# ProPrj___2024-09-03.net
KiCad netlist of a schematic drawn in EasyEDA Pro
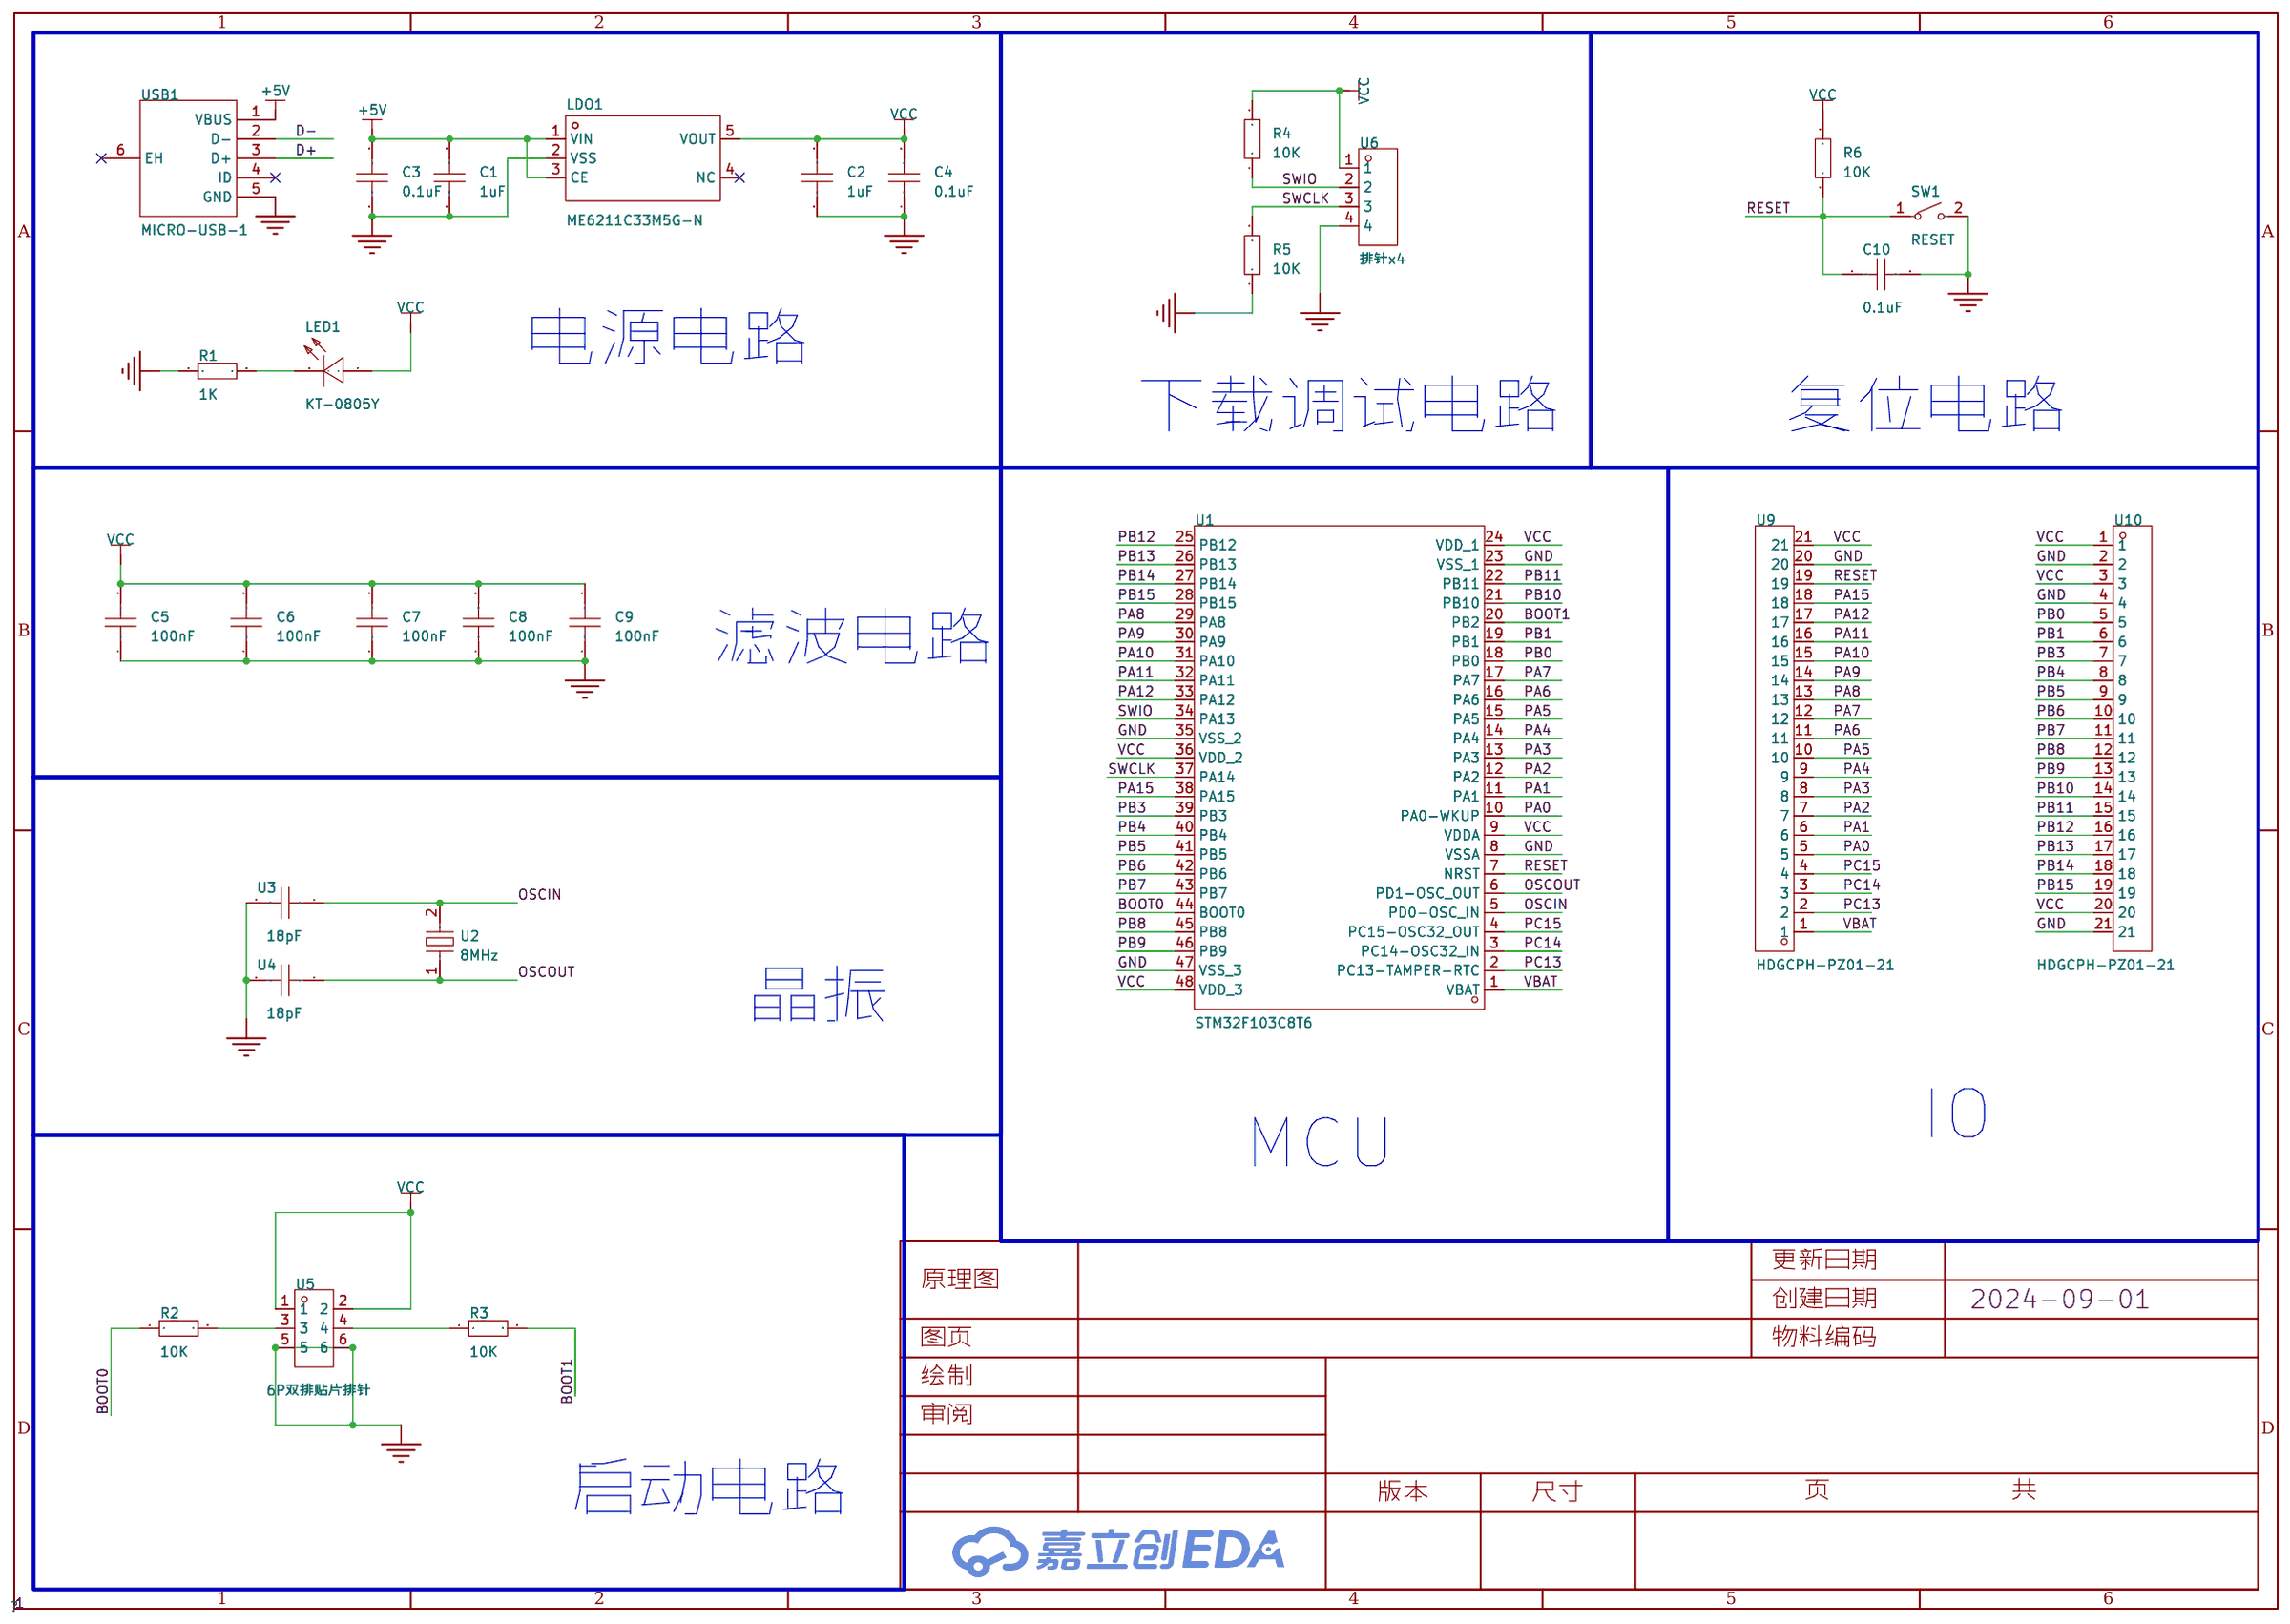
[diagram p0: schematic sheet]

(export (version "E")
  (design (tool "Eeschema 10.0.6"))
  (components
    (comp (ref "C1")
      (value "1uF")
      (footprint "easyedapro:C0603")
      (description "容值:1uF;精度:±10%;额定电压:50V;材质(温度系数):X5R;")
      (fields
        (field (name "Manufacturer Part") "CL10A105KB8NNNC")
        (field (name "Manufacturer") "SAMSUNG(三星)")
      )
      (libsource (lib "easyedapro") (part "CL10A105KB8NNNC"))
    )
    (comp (ref "C2")
      (value "1uF")
      (footprint "easyedapro:C0603")
      (description "容值:1uF;精度:±10%;额定电压:50V;材质(温度系数):X5R;")
      (fields
        (field (name "Manufacturer Part") "CL10A105KB8NNNC")
        (field (name "Manufacturer") "SAMSUNG(三星)")
      )
      (libsource (lib "easyedapro") (part "CL10A105KB8NNNC"))
    )
    (comp (ref "C3")
      (value "0.1uF")
      (footprint "easyedapro:C0603")
      (description "容值:1pF;额定电压:50V;材质(温度系数):C0G;")
      (fields (field (name "Manufacturer Part") "CGJ3E2C0G1H010C080AA") (field (name "Manufacturer") "TDK"))
      (libsource (lib "easyedapro") (part "CGJ3E2C0G1H010C080AA"))
    )
    (comp (ref "C4")
      (value "0.1uF")
      (footprint "easyedapro:C0603")
      (description "容值:1pF;额定电压:50V;材质(温度系数):C0G;")
      (fields (field (name "Manufacturer Part") "CGJ3E2C0G1H010C080AA") (field (name "Manufacturer") "TDK"))
      (libsource (lib "easyedapro") (part "CGJ3E2C0G1H010C080AA"))
    )
    (comp (ref "C5")
      (value "100nF")
      (footprint "easyedapro:C0603")
      (libsource (lib "easyedapro") (part "CapAcitance"))
    )
    (comp (ref "C6")
      (value "100nF")
      (footprint "easyedapro:C0603")
      (libsource (lib "easyedapro") (part "CapAcitance"))
    )
    (comp (ref "C7")
      (value "100nF")
      (footprint "easyedapro:C0603")
      (libsource (lib "easyedapro") (part "CapAcitance"))
    )
    (comp (ref "C8")
      (value "100nF")
      (footprint "easyedapro:C0603")
      (libsource (lib "easyedapro") (part "CapAcitance"))
    )
    (comp (ref "C9")
      (value "100nF")
      (footprint "easyedapro:C0603")
      (libsource (lib "easyedapro") (part "CapAcitance"))
    )
    (comp (ref "C10")
      (value "0.1uF")
      (footprint "easyedapro:C0603")
      (description "容值:1uF;精度:±10%;额定电压:50V;材质(温度系数):X5R;")
      (fields
        (field (name "Manufacturer Part") "CL10A105KB8NNNC")
        (field (name "Manufacturer") "SAMSUNG(三星)")
      )
      (libsource (lib "easyedapro") (part "CL10A105KB8NNNC"))
    )
    (comp (ref "LDO1")
      (value "ME6211C33M5G-N")
      (footprint "easyedapro:SOT-23-5_L3.0-W1.7-P0.95-LS2.8-BL")
      (description "输出类型:固定;最大输入电压:6V;输出电压:3.3V;最大输出电流:500mA;电源纹波抑制比(PSRR):70dB;输出极性:正极;")
      (fields (field (name "Manufacturer") "MICRONE(南京微盟)"))
      (libsource (lib "easyedapro") (part "ME6211C33M5G-N"))
    )
    (comp (ref "LED1")
      (value "KT-0805Y")
      (footprint "easyedapro:LED0805-R-RD")
      (description "发光颜色:黄色;功率:-;正向电流:-;主波长:-;二极管配置:-;透镜颜色:-;色温:-;发光角度:-;载带方式:-;工作温度:-;")
      (fields (field (name "Manufacturer") "KENTO"))
      (libsource (lib "easyedapro") (part "17-21SUYC/TR8"))
    )
    (comp (ref "R1") (value "1K") (footprint "easyedapro:R0603") (libsource (lib "easyedapro") (part "电阻")))
    (comp (ref "R2") (value "10K") (footprint "easyedapro:R0603") (libsource (lib "easyedapro") (part "电阻")))
    (comp (ref "R3") (value "10K") (footprint "easyedapro:R0603") (libsource (lib "easyedapro") (part "电阻")))
    (comp (ref "R4") (value "10K") (footprint "easyedapro:R0603") (libsource (lib "easyedapro") (part "电阻")))
    (comp (ref "R5") (value "10K") (footprint "easyedapro:R0603") (libsource (lib "easyedapro") (part "电阻")))
    (comp (ref "R6") (value "10K") (footprint "easyedapro:R0603") (libsource (lib "easyedapro") (part "电阻")))
    (comp (ref "SW1")
      (value "RESET")
      (footprint "easyedapro:SW-SMD_L6.0-W3.3-LS8.0")
      (libsource (lib "easyedapro") (part "SW_PB2_A1"))
    )
    (comp (ref "U1")
      (value "STM32F103C8T6")
      (footprint "easyedapro:LQFP-48_L7.0-W7.0-P0.50-LS9.0-BL")
      (description "CPU内核:ARM-M3;程序存储容量:64KB;RAM总容量:20KB;GPIO端口数量:37;工作电压范围:2V~3.6V;CPU最大主频:72MHz;程序存储器类型:FLASH;")
      (fields (field (name "Manufacturer") "ST(意法半导体)"))
      (libsource (lib "easyedapro") (part "STM32F103C8T6"))
    )
    (comp (ref "U2")
      (value "8MHz")
      (footprint "easyedapro:HC-49S_L10.6-W4.2-P4.85")
      (description "频率:6.7458MHz;常温频差:±20ppm;外接负载电容:20pF;频率稳定度(全温):±50ppm;")
      (fields
        (field (name "Manufacturer Part") "HY67458M49SOB2T02")
        (field (name "Manufacturer") "Huiyuan crystal(惠源晶工)")
      )
      (libsource (lib "easyedapro") (part "HY67458M49SOB2T02"))
    )
    (comp (ref "U3")
      (value "18pF")
      (footprint "easyedapro:C0603")
      (description "容值:1pF;额定电压:50V;材质(温度系数):C0G;")
      (fields (field (name "Manufacturer Part") "CGJ3E2C0G1H010C080AA") (field (name "Manufacturer") "TDK"))
      (libsource (lib "easyedapro") (part "CGJ3E2C0G1H010C080AA"))
    )
    (comp (ref "U4")
      (value "18pF")
      (footprint "easyedapro:C0603")
      (description "容值:1pF;额定电压:50V;材质(温度系数):C0G;")
      (fields (field (name "Manufacturer Part") "CGJ3E2C0G1H010C080AA") (field (name "Manufacturer") "TDK"))
      (libsource (lib "easyedapro") (part "CGJ3E2C0G1H010C080AA"))
    )
    (comp (ref "U5")
      (value "6P双排贴片排针")
      (footprint "easyedapro:HDR-SMD_6P-P2.54-V-M-R2-C3-LS7.6")
      (libsource (lib "easyedapro") (part "6P双排贴片排针"))
    )
    (comp (ref "U6")
      (value "排针x4")
      (footprint "easyedapro:HDR-TH_4P-P2.54-V-M-1")
      (libsource (lib "easyedapro") (part "排针X4"))
    )
    (comp (ref "U9")
      (value "HDGCPH-PZ01-21")
      (footprint "easyedapro:HDR-TH_21P-P2.54-V-M")
      (fields (field (name "Manufacturer") "HDGC(华德共创)"))
      (libsource (lib "easyedapro") (part "HDGCPH-PZ01- 21"))
    )
    (comp (ref "U10")
      (value "HDGCPH-PZ01-21")
      (footprint "easyedapro:HDR-TH_21P-P2.54-V-M")
      (fields (field (name "Manufacturer") "HDGC(华德共创)"))
      (libsource (lib "easyedapro") (part "HDGCPH-PZ01- 21"))
    )
    (comp (ref "USB1")
      (value "MICRO-USB-1")
      (footprint "easyedapro:MICRO-USB-SMD_C9900008946")
      (libsource (lib "easyedapro") (part "MICRO-USB-1"))
    )
  )
  (nets
    (net (code "1") (name "+5V") (class "Default")
      (node (ref "C1") (pin "2") (pinfunction "2_2") (pintype "unspecified"))
      (node (ref "C3") (pin "2") (pinfunction "2_2") (pintype "unspecified"))
      (node (ref "LDO1") (pin "1") (pinfunction "VIN_1") (pintype "input"))
      (node (ref "LDO1") (pin "3") (pinfunction "CE_3") (pintype "input"))
      (node (ref "USB1") (pin "1") (pinfunction "VBUS_1") (pintype "input"))
    )
    (net (code "2") (name "/BOOT0") (class "Default")
      (node (ref "R2") (pin "1") (pinfunction "1_1") (pintype "input"))
      (node (ref "U1") (pin "44") (pinfunction "BOOT0_44") (pintype "unspecified"))
    )
    (net (code "3") (name "/BOOT1") (class "Default")
      (node (ref "R3") (pin "2") (pinfunction "2_2") (pintype "input"))
      (node (ref "U1") (pin "20") (pinfunction "PB2_20") (pintype "unspecified"))
    )
    (net (code "4") (name "/D+") (class "Default")
      (node (ref "USB1") (pin "3") (pinfunction "D+_3") (pintype "input"))
    )
    (net (code "5") (name "/D-") (class "Default")
      (node (ref "USB1") (pin "2") (pinfunction "D-_2") (pintype "input"))
    )
    (net (code "6") (name "/OSCIN") (class "Default")
      (node (ref "U1") (pin "5") (pinfunction "PD0-OSC_IN_5") (pintype "unspecified"))
      (node (ref "U2") (pin "2") (pinfunction "GND_2") (pintype "input"))
      (node (ref "U3") (pin "1") (pinfunction "1_1") (pintype "unspecified"))
    )
    (net (code "7") (name "/OSCOUT") (class "Default")
      (node (ref "U1") (pin "6") (pinfunction "PD1-OSC_OUT_6") (pintype "unspecified"))
      (node (ref "U2") (pin "1") (pinfunction "1_1") (pintype "input"))
      (node (ref "U4") (pin "1") (pinfunction "1_1") (pintype "unspecified"))
    )
    (net (code "8") (name "/PA0") (class "Default")
      (node (ref "U1") (pin "10") (pinfunction "PA0-WKUP_10") (pintype "unspecified"))
      (node (ref "U9") (pin "5") (pinfunction "5_5") (pintype "unspecified"))
    )
    (net (code "9") (name "/PA1") (class "Default")
      (node (ref "U1") (pin "11") (pinfunction "PA1_11") (pintype "unspecified"))
      (node (ref "U9") (pin "6") (pinfunction "6_6") (pintype "unspecified"))
    )
    (net (code "10") (name "/PA2") (class "Default")
      (node (ref "U1") (pin "12") (pinfunction "PA2_12") (pintype "unspecified"))
      (node (ref "U9") (pin "7") (pinfunction "7_7") (pintype "unspecified"))
    )
    (net (code "11") (name "/PA3") (class "Default")
      (node (ref "U1") (pin "13") (pinfunction "PA3_13") (pintype "unspecified"))
      (node (ref "U9") (pin "8") (pinfunction "8_8") (pintype "unspecified"))
    )
    (net (code "12") (name "/PA4") (class "Default")
      (node (ref "U1") (pin "14") (pinfunction "PA4_14") (pintype "unspecified"))
      (node (ref "U9") (pin "9") (pinfunction "9_9") (pintype "unspecified"))
    )
    (net (code "13") (name "/PA5") (class "Default")
      (node (ref "U1") (pin "15") (pinfunction "PA5_15") (pintype "unspecified"))
      (node (ref "U9") (pin "10") (pinfunction "10_10") (pintype "unspecified"))
    )
    (net (code "14") (name "/PA6") (class "Default")
      (node (ref "U1") (pin "16") (pinfunction "PA6_16") (pintype "unspecified"))
      (node (ref "U9") (pin "11") (pinfunction "11_11") (pintype "unspecified"))
    )
    (net (code "15") (name "/PA7") (class "Default")
      (node (ref "U1") (pin "17") (pinfunction "PA7_17") (pintype "unspecified"))
      (node (ref "U9") (pin "12") (pinfunction "12_12") (pintype "unspecified"))
    )
    (net (code "16") (name "/PA8") (class "Default")
      (node (ref "U1") (pin "29") (pinfunction "PA8_29") (pintype "unspecified"))
      (node (ref "U9") (pin "13") (pinfunction "13_13") (pintype "unspecified"))
    )
    (net (code "17") (name "/PA9") (class "Default")
      (node (ref "U1") (pin "30") (pinfunction "PA9_30") (pintype "unspecified"))
      (node (ref "U9") (pin "14") (pinfunction "14_14") (pintype "unspecified"))
    )
    (net (code "18") (name "/PA10") (class "Default")
      (node (ref "U1") (pin "31") (pinfunction "PA10_31") (pintype "unspecified"))
      (node (ref "U9") (pin "15") (pinfunction "15_15") (pintype "unspecified"))
    )
    (net (code "19") (name "/PA11") (class "Default")
      (node (ref "U1") (pin "32") (pinfunction "PA11_32") (pintype "unspecified"))
      (node (ref "U9") (pin "16") (pinfunction "16_16") (pintype "unspecified"))
    )
    (net (code "20") (name "/PA12") (class "Default")
      (node (ref "U1") (pin "33") (pinfunction "PA12_33") (pintype "unspecified"))
      (node (ref "U9") (pin "17") (pinfunction "17_17") (pintype "unspecified"))
    )
    (net (code "21") (name "/PA15") (class "Default")
      (node (ref "U1") (pin "38") (pinfunction "PA15_38") (pintype "unspecified"))
      (node (ref "U9") (pin "18") (pinfunction "18_18") (pintype "unspecified"))
    )
    (net (code "22") (name "/PB0") (class "Default")
      (node (ref "U1") (pin "18") (pinfunction "PB0_18") (pintype "unspecified"))
      (node (ref "U10") (pin "5") (pinfunction "5_5") (pintype "unspecified"))
    )
    (net (code "23") (name "/PB1") (class "Default")
      (node (ref "U1") (pin "19") (pinfunction "PB1_19") (pintype "unspecified"))
      (node (ref "U10") (pin "6") (pinfunction "6_6") (pintype "unspecified"))
    )
    (net (code "24") (name "/PB3") (class "Default")
      (node (ref "U1") (pin "39") (pinfunction "PB3_39") (pintype "unspecified"))
      (node (ref "U10") (pin "7") (pinfunction "7_7") (pintype "unspecified"))
    )
    (net (code "25") (name "/PB4") (class "Default")
      (node (ref "U1") (pin "40") (pinfunction "PB4_40") (pintype "unspecified"))
      (node (ref "U10") (pin "8") (pinfunction "8_8") (pintype "unspecified"))
    )
    (net (code "26") (name "/PB5") (class "Default")
      (node (ref "U1") (pin "41") (pinfunction "PB5_41") (pintype "unspecified"))
      (node (ref "U10") (pin "9") (pinfunction "9_9") (pintype "unspecified"))
    )
    (net (code "27") (name "/PB6") (class "Default")
      (node (ref "U1") (pin "42") (pinfunction "PB6_42") (pintype "unspecified"))
      (node (ref "U10") (pin "10") (pinfunction "10_10") (pintype "unspecified"))
    )
    (net (code "28") (name "/PB7") (class "Default")
      (node (ref "U1") (pin "43") (pinfunction "PB7_43") (pintype "unspecified"))
      (node (ref "U10") (pin "11") (pinfunction "11_11") (pintype "unspecified"))
    )
    (net (code "29") (name "/PB8") (class "Default")
      (node (ref "U1") (pin "45") (pinfunction "PB8_45") (pintype "unspecified"))
      (node (ref "U10") (pin "12") (pinfunction "12_12") (pintype "unspecified"))
    )
    (net (code "30") (name "/PB9") (class "Default")
      (node (ref "U1") (pin "46") (pinfunction "PB9_46") (pintype "unspecified"))
      (node (ref "U10") (pin "13") (pinfunction "13_13") (pintype "unspecified"))
    )
    (net (code "31") (name "/PB10") (class "Default")
      (node (ref "U1") (pin "21") (pinfunction "PB10_21") (pintype "unspecified"))
      (node (ref "U10") (pin "14") (pinfunction "14_14") (pintype "unspecified"))
    )
    (net (code "32") (name "/PB11") (class "Default")
      (node (ref "U1") (pin "22") (pinfunction "PB11_22") (pintype "unspecified"))
      (node (ref "U10") (pin "15") (pinfunction "15_15") (pintype "unspecified"))
    )
    (net (code "33") (name "/PB12") (class "Default")
      (node (ref "U1") (pin "25") (pinfunction "PB12_25") (pintype "unspecified"))
      (node (ref "U10") (pin "16") (pinfunction "16_16") (pintype "unspecified"))
    )
    (net (code "34") (name "/PB13") (class "Default")
      (node (ref "U1") (pin "26") (pinfunction "PB13_26") (pintype "unspecified"))
      (node (ref "U10") (pin "17") (pinfunction "17_17") (pintype "unspecified"))
    )
    (net (code "35") (name "/PB14") (class "Default")
      (node (ref "U1") (pin "27") (pinfunction "PB14_27") (pintype "unspecified"))
      (node (ref "U10") (pin "18") (pinfunction "18_18") (pintype "unspecified"))
    )
    (net (code "36") (name "/PB15") (class "Default")
      (node (ref "U1") (pin "28") (pinfunction "PB15_28") (pintype "unspecified"))
      (node (ref "U10") (pin "19") (pinfunction "19_19") (pintype "unspecified"))
    )
    (net (code "37") (name "/PC13") (class "Default")
      (node (ref "U1") (pin "2") (pinfunction "PC13-TAMPER-RTC_2") (pintype "unspecified"))
      (node (ref "U9") (pin "2") (pinfunction "2_2") (pintype "unspecified"))
    )
    (net (code "38") (name "/PC14") (class "Default")
      (node (ref "U1") (pin "3") (pinfunction "PC14-OSC32_IN_3") (pintype "unspecified"))
      (node (ref "U9") (pin "3") (pinfunction "3_3") (pintype "unspecified"))
    )
    (net (code "39") (name "/PC15") (class "Default")
      (node (ref "U1") (pin "4") (pinfunction "PC15-OSC32_OUT_4") (pintype "unspecified"))
      (node (ref "U9") (pin "4") (pinfunction "4_4") (pintype "unspecified"))
    )
    (net (code "40") (name "/RESET") (class "Default")
      (node (ref "C10") (pin "1") (pinfunction "1_1") (pintype "unspecified"))
      (node (ref "R6") (pin "1") (pinfunction "1_1") (pintype "input"))
      (node (ref "SW1") (pin "1") (pinfunction "1_1") (pintype "unspecified"))
      (node (ref "U1") (pin "7") (pinfunction "NRST_7") (pintype "unspecified"))
      (node (ref "U9") (pin "19") (pinfunction "19_19") (pintype "unspecified"))
    )
    (net (code "41") (name "/SWCLK") (class "Default")
      (node (ref "R5") (pin "2") (pinfunction "2_2") (pintype "input"))
      (node (ref "U1") (pin "37") (pinfunction "PA14_37") (pintype "unspecified"))
      (node (ref "U6") (pin "3") (pinfunction "3_3") (pintype "unspecified"))
    )
    (net (code "42") (name "/SWIO") (class "Default")
      (node (ref "R4") (pin "1") (pinfunction "1_1") (pintype "input"))
      (node (ref "U1") (pin "34") (pinfunction "PA13_34") (pintype "unspecified"))
      (node (ref "U6") (pin "2") (pinfunction "2_2") (pintype "unspecified"))
    )
    (net (code "43") (name "/VBAT") (class "Default")
      (node (ref "U1") (pin "1") (pinfunction "VBAT_1") (pintype "unspecified"))
      (node (ref "U9") (pin "1") (pinfunction "1_1") (pintype "unspecified"))
    )
    (net (code "44") (name "GND") (class "Default")
      (node (ref "C1") (pin "1") (pinfunction "1_1") (pintype "unspecified"))
      (node (ref "C10") (pin "2") (pinfunction "2_2") (pintype "unspecified"))
      (node (ref "C2") (pin "1") (pinfunction "1_1") (pintype "unspecified"))
      (node (ref "C3") (pin "1") (pinfunction "1_1") (pintype "unspecified"))
      (node (ref "C4") (pin "1") (pinfunction "1_1") (pintype "unspecified"))
      (node (ref "C5") (pin "1") (pinfunction "1_1") (pintype "input"))
      (node (ref "C6") (pin "1") (pinfunction "1_1") (pintype "input"))
      (node (ref "C7") (pin "1") (pinfunction "1_1") (pintype "input"))
      (node (ref "C8") (pin "1") (pinfunction "1_1") (pintype "input"))
      (node (ref "C9") (pin "1") (pinfunction "1_1") (pintype "input"))
      (node (ref "LDO1") (pin "2") (pinfunction "VSS_2") (pintype "input"))
      (node (ref "R1") (pin "1") (pinfunction "1_1") (pintype "input"))
      (node (ref "R5") (pin "1") (pinfunction "1_1") (pintype "input"))
      (node (ref "SW1") (pin "2") (pinfunction "2_2") (pintype "unspecified"))
      (node (ref "U1") (pin "23") (pinfunction "VSS_1_23") (pintype "unspecified"))
      (node (ref "U1") (pin "35") (pinfunction "VSS_2_35") (pintype "unspecified"))
      (node (ref "U1") (pin "47") (pinfunction "VSS_3_47") (pintype "unspecified"))
      (node (ref "U1") (pin "8") (pinfunction "VSSA_8") (pintype "unspecified"))
      (node (ref "U10") (pin "2") (pinfunction "2_2") (pintype "unspecified"))
      (node (ref "U10") (pin "21") (pinfunction "21_21") (pintype "unspecified"))
      (node (ref "U10") (pin "4") (pinfunction "4_4") (pintype "unspecified"))
      (node (ref "U3") (pin "2") (pinfunction "2_2") (pintype "unspecified"))
      (node (ref "U4") (pin "2") (pinfunction "2_2") (pintype "unspecified"))
      (node (ref "U5") (pin "5") (pinfunction "5_5") (pintype "input"))
      (node (ref "U5") (pin "6") (pinfunction "6_6") (pintype "input"))
      (node (ref "U6") (pin "4") (pinfunction "4_4") (pintype "unspecified"))
      (node (ref "U9") (pin "20") (pinfunction "20_20") (pintype "unspecified"))
      (node (ref "USB1") (pin "5") (pinfunction "GND_5") (pintype "input"))
    )
    (net (code "45") (name "Net-(LED1--)") (class "Default")
      (node (ref "LED1") (pin "2") (pinfunction "-_2") (pintype "unspecified"))
      (node (ref "R1") (pin "2") (pinfunction "2_2") (pintype "input"))
    )
    (net (code "46") (name "Net-(R2-Pad2)") (class "Default")
      (node (ref "R2") (pin "2") (pinfunction "2_2") (pintype "input"))
      (node (ref "U5") (pin "3") (pinfunction "3_3") (pintype "input"))
    )
    (net (code "47") (name "Net-(R3-Pad1)") (class "Default")
      (node (ref "R3") (pin "1") (pinfunction "1_1") (pintype "input"))
      (node (ref "U5") (pin "4") (pinfunction "4_4") (pintype "input"))
    )
    (net (code "48") (name "VCC") (class "Default")
      (node (ref "C2") (pin "2") (pinfunction "2_2") (pintype "unspecified"))
      (node (ref "C4") (pin "2") (pinfunction "2_2") (pintype "unspecified"))
      (node (ref "C5") (pin "2") (pinfunction "2_2") (pintype "input"))
      (node (ref "C6") (pin "2") (pinfunction "2_2") (pintype "input"))
      (node (ref "C7") (pin "2") (pinfunction "2_2") (pintype "input"))
      (node (ref "C8") (pin "2") (pinfunction "2_2") (pintype "input"))
      (node (ref "C9") (pin "2") (pinfunction "2_2") (pintype "input"))
      (node (ref "LDO1") (pin "5") (pinfunction "VOUT_5") (pintype "input"))
      (node (ref "LED1") (pin "1") (pinfunction "+_1") (pintype "unspecified"))
      (node (ref "R4") (pin "2") (pinfunction "2_2") (pintype "input"))
      (node (ref "R6") (pin "2") (pinfunction "2_2") (pintype "input"))
      (node (ref "U1") (pin "24") (pinfunction "VDD_1_24") (pintype "unspecified"))
      (node (ref "U1") (pin "36") (pinfunction "VDD_2_36") (pintype "unspecified"))
      (node (ref "U1") (pin "48") (pinfunction "VDD_3_48") (pintype "unspecified"))
      (node (ref "U1") (pin "9") (pinfunction "VDDA_9") (pintype "unspecified"))
      (node (ref "U10") (pin "1") (pinfunction "1_1") (pintype "unspecified"))
      (node (ref "U10") (pin "20") (pinfunction "20_20") (pintype "unspecified"))
      (node (ref "U10") (pin "3") (pinfunction "3_3") (pintype "unspecified"))
      (node (ref "U5") (pin "1") (pinfunction "1_1") (pintype "input"))
      (node (ref "U5") (pin "2") (pinfunction "2_2") (pintype "input"))
      (node (ref "U6") (pin "1") (pinfunction "1_1") (pintype "unspecified"))
      (node (ref "U9") (pin "21") (pinfunction "21_21") (pintype "unspecified"))
    )
    (net (code "49") (name "unconnected-(LDO1-NC-Pad4)") (class "Default")
      (node (ref "LDO1") (pin "4") (pinfunction "NC_4") (pintype "input+no_connect"))
    )
    (net (code "50") (name "unconnected-(USB1-EH-Pad6)") (class "Default")
      (node (ref "USB1") (pin "6") (pinfunction "EH_6") (pintype "input+no_connect"))
    )
    (net (code "51") (name "unconnected-(USB1-ID-Pad4)") (class "Default")
      (node (ref "USB1") (pin "4") (pinfunction "ID_4") (pintype "input+no_connect"))
    )
  )
)
